# Controller.net
KiCad netlist of a schematic drawn in Altium Designer
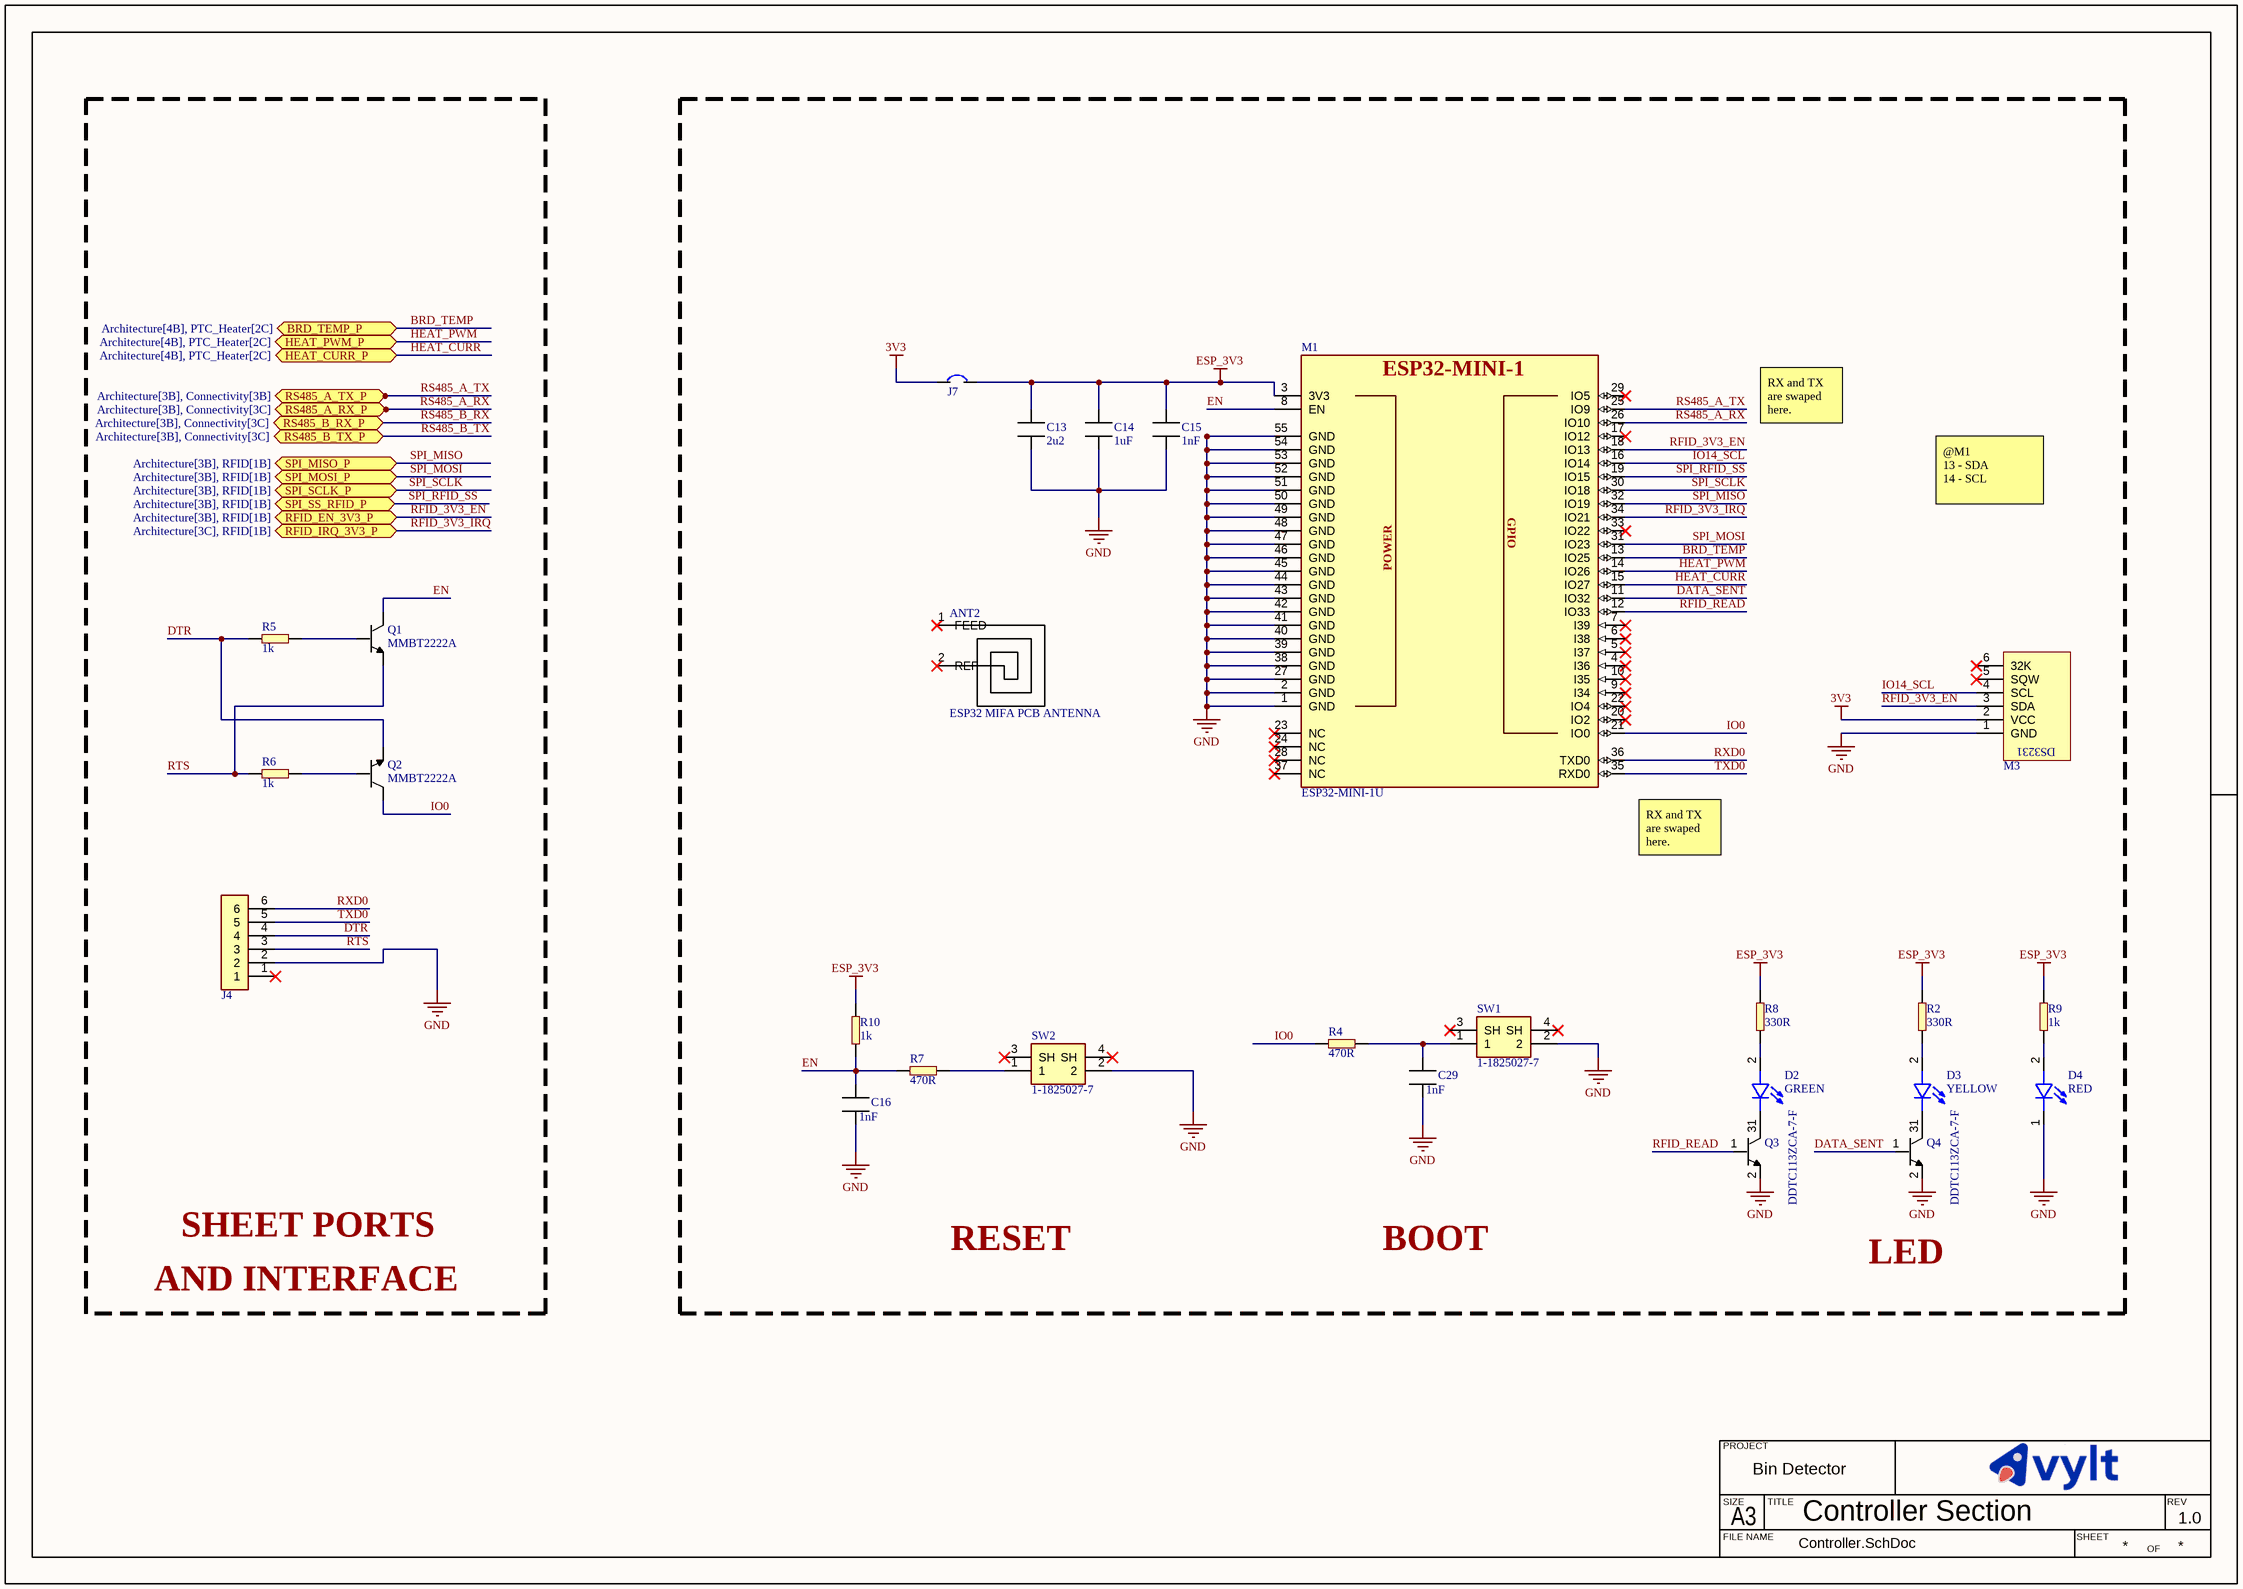
[diagram p0: Controller.SchDoc]

(export (version "E")
  (design (tool "Eeschema 10.0.6"))
  (components
    (comp (ref "ANT2")
      (value "ESP32 MIFA PCB ANTENNA")
      (footprint "ESP32 MIFA PCB ANTENNA")
      (libsource (lib "Antenna") (part "ESP32 MIFA PCB ANTENNA"))
    )
    (comp (ref "C13")
      (value "2u2")
      (footprint "CAPC1608X10N")
      (description "MLCC 0603")
      (fields (field (name "Comment") "ERP_102-1"))
      (libsource (lib "Capacitor") (part "MLCC_0603"))
    )
    (comp (ref "C14")
      (value "1uF")
      (footprint "CAPC1608X10N")
      (description "MLCC 0603")
      (fields (field (name "Comment") "ERP_102-1"))
      (libsource (lib "Capacitor") (part "MLCC_0603"))
    )
    (comp (ref "C15")
      (value "1nF")
      (footprint "CAPC1608X10N")
      (description "MLCC 0603")
      (fields (field (name "Comment") "ERP_102-1"))
      (libsource (lib "Capacitor") (part "MLCC_0603"))
    )
    (comp (ref "C16")
      (value "1nF")
      (footprint "CAPC1608X10N")
      (description "MLCC 0603")
      (fields (field (name "Comment") "ERP_102-1"))
      (libsource (lib "Capacitor") (part "MLCC_0603"))
    )
    (comp (ref "C29")
      (value "1nF")
      (footprint "CAPC1608X10N")
      (description "MLCC 0603")
      (fields (field (name "Comment") "ERP_102-1"))
      (libsource (lib "Capacitor") (part "MLCC_0603"))
    )
    (comp (ref "D2")
      (value "GREEN")
      (footprint "LED_2SMD")
      (description "LED GREEN CLEAR 1204 SMD R/A")
      (fields (field (name "Comment") "LED_2SMD"))
      (libsource (lib "LED") (part "LED_2SMD"))
    )
    (comp (ref "D3")
      (value "YELLOW")
      (footprint "LED_2SMD")
      (description "LED YELLOW CLEAR 1204 SMD R/A")
      (fields (field (name "Comment") "LED_2SMD"))
      (libsource (lib "LED") (part "LED_2SMD"))
    )
    (comp (ref "D4")
      (value "RED")
      (footprint "LED_2SMD")
      (description "LED RED CLEAR 1204 SMD R/A")
      (fields (field (name "Comment") "LED_2SMD"))
      (libsource (lib "LED") (part "LED_2SMD"))
    )
    (comp (ref "J4")
      (value "ERP_148-2")
      (footprint "6PX1R")
      (description "6PX1R")
      (libsource (lib "Male_Header_P2.54") (part "6PX1R"))
    )
    (comp (ref "J7")
      (value "Jumper_2P")
      (footprint "Jumper_2P")
      (description "Jumper 2 Pins")
      (libsource (lib "Jumper") (part "Jumper_2P"))
    )
    (comp (ref "M1")
      (value "ESP32-MINI-1U")
      (footprint "ESP32_MINI_1U")
      (description "ESP32_C3_MINI_1 Module")
      (fields (field (name "Comment") "ERP_140-3"))
      (libsource (lib "ESP") (part "ESP32_MINI_1"))
    )
    (comp (ref "M3")
      (value "DS3231_HW-084")
      (footprint "DS3231_HW-084")
      (description "DS3231 Time Module , HW-084")
      (libsource (lib "Time") (part "DS3231_HW-084"))
    )
    (comp (ref "Q1")
      (value "MMBT2222A")
      (footprint "MMBT2222")
      (fields (field (name "Comment") "ERP_105-1"))
      (libsource (lib "BJT") (part "MMBT2222"))
    )
    (comp (ref "Q2")
      (value "MMBT2222A")
      (footprint "MMBT2222")
      (fields (field (name "Comment") "ERP_105-1"))
      (libsource (lib "BJT") (part "MMBT2222"))
    )
    (comp (ref "Q3")
      (value "DDTC113ZCA-7-F")
      (footprint "DDTCXXXXCA")
      (description "TRANS PREBIAS NPN 50V SOT23-3")
      (fields (field (name "Comment") "ERP_105-1"))
      (libsource (lib "BJT") (part "DDTCXXXXCA"))
    )
    (comp (ref "Q4")
      (value "DDTC113ZCA-7-F")
      (footprint "DDTCXXXXCA")
      (description "TRANS PREBIAS NPN 50V SOT23-3")
      (fields (field (name "Comment") "ERP_105-1"))
      (libsource (lib "BJT") (part "DDTCXXXXCA"))
    )
    (comp (ref "R2")
      (value "330R")
      (footprint "RES_0603")
      (description "RES_0603")
      (fields (field (name "Comment") "ERP_101-1"))
      (libsource (lib "") (part "RES_0603_1"))
    )
    (comp (ref "R4")
      (value "470R")
      (footprint "RES_0603")
      (description "RES_0603")
      (fields (field (name "Comment") "ERP_101-1"))
      (libsource (lib "Resistor") (part "RES_0603"))
    )
    (comp (ref "R5")
      (value "1k")
      (footprint "RES_0603")
      (description "RES_0603")
      (fields (field (name "Comment") "ERP_101-1"))
      (libsource (lib "Resistor") (part "RES_0603"))
    )
    (comp (ref "R6")
      (value "1k")
      (footprint "RES_0603")
      (description "RES_0603")
      (fields (field (name "Comment") "ERP_101-1"))
      (libsource (lib "Resistor") (part "RES_0603"))
    )
    (comp (ref "R7")
      (value "470R")
      (footprint "RES_0603")
      (description "RES_0603")
      (fields (field (name "Comment") "ERP_101-1"))
      (libsource (lib "Resistor") (part "RES_0603"))
    )
    (comp (ref "R8")
      (value "330R")
      (footprint "RES_0603")
      (description "RES_0603")
      (fields (field (name "Comment") "ERP_101-1"))
      (libsource (lib "") (part "RES_0603_1"))
    )
    (comp (ref "R9")
      (value "1k")
      (footprint "RES_0603")
      (description "RES_0603")
      (fields (field (name "Comment") "ERP_101-1"))
      (libsource (lib "") (part "RES_0603_1"))
    )
    (comp (ref "R10")
      (value "1k")
      (footprint "RES_0603")
      (description "RES_0603")
      (fields (field (name "Comment") "ERP_101-1"))
      (libsource (lib "") (part "RES_0603_1"))
    )
    (comp (ref "SW1")
      (value "1-1825027-7")
      (footprint "FSM_6X6")
      (fields (field (name "Comment") "ERP_110-4"))
      (libsource (lib "Switch") (part "FSM_6X6"))
    )
    (comp (ref "SW2")
      (value "1-1825027-7")
      (footprint "FSM_6X6")
      (fields (field (name "Comment") "ERP_110-4"))
      (libsource (lib "Switch") (part "FSM_6X6"))
    )
  )
  (nets
    (net (code "2") (name "/BRD_TEMP") (class "Default")
      (node (ref "M1") (pin "13") (pinfunction "IO25_13") (pintype "bidirectional"))
    )
    (net (code "3") (name "/DATA_SENT") (class "Default")
      (node (ref "M1") (pin "11") (pinfunction "IO32_11") (pintype "bidirectional"))
      (node (ref "Q4") (pin "1") (pinfunction "1_1") (pintype "passive"))
    )
    (net (code "4") (name "/DTR") (class "Default")
      (node (ref "J4") (pin "4") (pinfunction "4_4") (pintype "passive"))
      (node (ref "Q2") (pin "2") (pinfunction "2_2") (pintype "passive"))
      (node (ref "R5") (pin "2") (pinfunction "2_2") (pintype "passive"))
    )
    (net (code "5") (name "/EN") (class "Default")
      (node (ref "C16") (pin "1") (pinfunction "1_1") (pintype "passive"))
      (node (ref "M1") (pin "8") (pinfunction "EN_8") (pintype "passive"))
      (node (ref "Q1") (pin "3") (pinfunction "3_3") (pintype "passive"))
      (node (ref "R10") (pin "1") (pinfunction "1_1") (pintype "passive"))
      (node (ref "R7") (pin "2") (pinfunction "2_2") (pintype "passive"))
    )
    (net (code "6") (name "/HEAT_CURR") (class "Default")
      (node (ref "M1") (pin "15") (pinfunction "IO27_15") (pintype "bidirectional"))
    )
    (net (code "7") (name "/HEAT_PWM") (class "Default")
      (node (ref "M1") (pin "14") (pinfunction "IO26_14") (pintype "bidirectional"))
    )
    (net (code "8") (name "/IO0") (class "Default")
      (node (ref "M1") (pin "21") (pinfunction "IO0_21") (pintype "bidirectional"))
      (node (ref "Q2") (pin "3") (pinfunction "3_3") (pintype "passive"))
      (node (ref "R4") (pin "2") (pinfunction "2_2") (pintype "passive"))
    )
    (net (code "9") (name "/IO14_SCL") (class "Default")
      (node (ref "M1") (pin "16") (pinfunction "IO14_16") (pintype "bidirectional"))
      (node (ref "M3") (pin "4") (pinfunction "SCL_4") (pintype "passive"))
    )
    (net (code "10") (name "/RFID_3V3_EN") (class "Default")
      (node (ref "M1") (pin "18") (pinfunction "IO13_18") (pintype "bidirectional"))
      (node (ref "M3") (pin "3") (pinfunction "SDA_3") (pintype "passive"))
    )
    (net (code "11") (name "/RFID_3V3_IRQ") (class "Default")
      (node (ref "M1") (pin "34") (pinfunction "IO21_34") (pintype "bidirectional"))
    )
    (net (code "12") (name "/RFID_READ") (class "Default")
      (node (ref "M1") (pin "12") (pinfunction "IO33_12") (pintype "bidirectional"))
      (node (ref "Q3") (pin "1") (pinfunction "1_1") (pintype "passive"))
    )
    (net (code "13") (name "/RS485_A_RX") (class "Default")
      (node (ref "M1") (pin "26") (pinfunction "IO10_26") (pintype "bidirectional"))
    )
    (net (code "14") (name "/RS485_A_TX") (class "Default")
      (node (ref "M1") (pin "25") (pinfunction "IO9_25") (pintype "bidirectional"))
    )
    (net (code "17") (name "/RTS") (class "Default")
      (node (ref "J4") (pin "3") (pinfunction "3_3") (pintype "passive"))
      (node (ref "Q1") (pin "2") (pinfunction "2_2") (pintype "passive"))
      (node (ref "R6") (pin "2") (pinfunction "2_2") (pintype "passive"))
    )
    (net (code "18") (name "/RXD0") (class "Default")
      (node (ref "J4") (pin "6") (pinfunction "6_6") (pintype "passive"))
      (node (ref "M1") (pin "36") (pinfunction "TXD0_36") (pintype "bidirectional"))
    )
    (net (code "19") (name "/SPI_MISO") (class "Default")
      (node (ref "M1") (pin "32") (pinfunction "IO19_32") (pintype "bidirectional"))
    )
    (net (code "20") (name "/SPI_MOSI") (class "Default")
      (node (ref "M1") (pin "31") (pinfunction "IO23_31") (pintype "bidirectional"))
    )
    (net (code "21") (name "/SPI_RFID_SS") (class "Default")
      (node (ref "M1") (pin "19") (pinfunction "IO15_19") (pintype "bidirectional"))
    )
    (net (code "22") (name "/SPI_SCLK") (class "Default")
      (node (ref "M1") (pin "30") (pinfunction "IO18_30") (pintype "bidirectional"))
    )
    (net (code "23") (name "/TXD0") (class "Default")
      (node (ref "J4") (pin "5") (pinfunction "5_5") (pintype "passive"))
      (node (ref "M1") (pin "35") (pinfunction "RXD0_35") (pintype "bidirectional"))
    )
    (net (code "24") (name "3V3") (class "Default")
      (node (ref "J7") (pin "1") (pintype "passive"))
      (node (ref "M3") (pin "2") (pinfunction "VCC_2") (pintype "passive"))
    )
    (net (code "25") (name "ESP_3V3") (class "Default")
      (node (ref "C13") (pin "2") (pinfunction "2_2") (pintype "passive"))
      (node (ref "C14") (pin "2") (pinfunction "2_2") (pintype "passive"))
      (node (ref "C15") (pin "2") (pinfunction "2_2") (pintype "passive"))
      (node (ref "J7") (pin "2") (pintype "passive"))
      (node (ref "M1") (pin "3") (pinfunction "3V3_3") (pintype "power_in"))
      (node (ref "R10") (pin "2") (pinfunction "2_2") (pintype "passive"))
      (node (ref "R2") (pin "2") (pinfunction "2_2") (pintype "passive"))
      (node (ref "R8") (pin "2") (pinfunction "2_2") (pintype "passive"))
      (node (ref "R9") (pin "2") (pinfunction "2_2") (pintype "passive"))
    )
    (net (code "26") (name "GND") (class "Default")
      (node (ref "C13") (pin "1") (pinfunction "1_1") (pintype "passive"))
      (node (ref "C14") (pin "1") (pinfunction "1_1") (pintype "passive"))
      (node (ref "C15") (pin "1") (pinfunction "1_1") (pintype "passive"))
      (node (ref "C16") (pin "2") (pinfunction "2_2") (pintype "passive"))
      (node (ref "C29") (pin "2") (pinfunction "2_2") (pintype "passive"))
      (node (ref "D4") (pin "1") (pinfunction "1_1") (pintype "passive"))
      (node (ref "J4") (pin "2") (pinfunction "2_2") (pintype "passive"))
      (node (ref "M1") (pin "1") (pinfunction "GND_1") (pintype "passive"))
      (node (ref "M1") (pin "2") (pinfunction "GND_2") (pintype "passive"))
      (node (ref "M1") (pin "27") (pinfunction "GND_27") (pintype "passive"))
      (node (ref "M1") (pin "38") (pinfunction "GND_38") (pintype "passive"))
      (node (ref "M1") (pin "39") (pinfunction "GND_39") (pintype "passive"))
      (node (ref "M1") (pin "40") (pinfunction "GND_40") (pintype "passive"))
      (node (ref "M1") (pin "41") (pinfunction "GND_41") (pintype "passive"))
      (node (ref "M1") (pin "42") (pinfunction "GND_42") (pintype "passive"))
      (node (ref "M1") (pin "43") (pinfunction "GND_43") (pintype "passive"))
      (node (ref "M1") (pin "44") (pinfunction "GND_44") (pintype "passive"))
      (node (ref "M1") (pin "45") (pinfunction "GND_45") (pintype "passive"))
      (node (ref "M1") (pin "46") (pinfunction "GND_46") (pintype "passive"))
      (node (ref "M1") (pin "47") (pinfunction "GND_47") (pintype "passive"))
      (node (ref "M1") (pin "48") (pinfunction "GND_48") (pintype "passive"))
      (node (ref "M1") (pin "49") (pinfunction "GND_49") (pintype "passive"))
      (node (ref "M1") (pin "50") (pinfunction "GND_50") (pintype "passive"))
      (node (ref "M1") (pin "51") (pinfunction "GND_51") (pintype "passive"))
      (node (ref "M1") (pin "52") (pinfunction "GND_52") (pintype "passive"))
      (node (ref "M1") (pin "53") (pinfunction "GND_53") (pintype "passive"))
      (node (ref "M1") (pin "54") (pinfunction "GND_54") (pintype "passive"))
      (node (ref "M1") (pin "55") (pinfunction "GND_55") (pintype "passive"))
      (node (ref "M3") (pin "1") (pinfunction "GND_1") (pintype "passive"))
      (node (ref "Q3") (pin "2") (pinfunction "2_2") (pintype "passive"))
      (node (ref "Q4") (pin "2") (pinfunction "2_2") (pintype "passive"))
      (node (ref "SW1") (pin "2") (pinfunction "2_2") (pintype "passive"))
      (node (ref "SW2") (pin "2") (pinfunction "2_2") (pintype "passive"))
    )
    (net (code "27") (name "Net-(C29-Pad1)") (class "Default")
      (node (ref "C29") (pin "1") (pinfunction "1_1") (pintype "passive"))
      (node (ref "R4") (pin "1") (pinfunction "1_1") (pintype "passive"))
      (node (ref "SW1") (pin "1") (pinfunction "1_1") (pintype "passive"))
    )
    (net (code "28") (name "Net-(D2-Pad1)") (class "Default")
      (node (ref "D2") (pin "1") (pinfunction "1_1") (pintype "passive"))
      (node (ref "Q3") (pin "3") (pinfunction "3_3") (pintype "passive"))
    )
    (net (code "29") (name "Net-(D2-Pad2)") (class "Default")
      (node (ref "D2") (pin "2") (pinfunction "2_2") (pintype "passive"))
      (node (ref "R8") (pin "1") (pinfunction "1_1") (pintype "passive"))
    )
    (net (code "30") (name "Net-(D3-Pad1)") (class "Default")
      (node (ref "D3") (pin "1") (pinfunction "1_1") (pintype "passive"))
      (node (ref "Q4") (pin "3") (pinfunction "3_3") (pintype "passive"))
    )
    (net (code "31") (name "Net-(D3-Pad2)") (class "Default")
      (node (ref "D3") (pin "2") (pinfunction "2_2") (pintype "passive"))
      (node (ref "R2") (pin "1") (pinfunction "1_1") (pintype "passive"))
    )
    (net (code "32") (name "Net-(D4-Pad2)") (class "Default")
      (node (ref "D4") (pin "2") (pinfunction "2_2") (pintype "passive"))
      (node (ref "R9") (pin "1") (pinfunction "1_1") (pintype "passive"))
    )
    (net (code "33") (name "Net-(Q1-Pad1)") (class "Default")
      (node (ref "Q1") (pin "1") (pinfunction "1_1") (pintype "passive"))
      (node (ref "R5") (pin "1") (pinfunction "1_1") (pintype "passive"))
    )
    (net (code "34") (name "Net-(Q2-Pad1)") (class "Default")
      (node (ref "Q2") (pin "1") (pinfunction "1_1") (pintype "passive"))
      (node (ref "R6") (pin "1") (pinfunction "1_1") (pintype "passive"))
    )
    (net (code "35") (name "Net-(R7-Pad1)") (class "Default")
      (node (ref "R7") (pin "1") (pinfunction "1_1") (pintype "passive"))
      (node (ref "SW2") (pin "1") (pinfunction "1_1") (pintype "passive"))
    )
    (net (code "36") (name "unconnected-(ANT2-FEED-Pad1)") (class "Default")
      (node (ref "ANT2") (pin "1") (pinfunction "FEED_1") (pintype "passive+no_connect"))
    )
    (net (code "37") (name "unconnected-(ANT2-REF-Pad2)") (class "Default")
      (node (ref "ANT2") (pin "2") (pinfunction "REF_2") (pintype "passive+no_connect"))
    )
    (net (code "38") (name "unconnected-(J4-Pad1)") (class "Default")
      (node (ref "J4") (pin "1") (pinfunction "1_1") (pintype "passive+no_connect"))
    )
    (net (code "39") (name "unconnected-(M1-I34-Pad9)") (class "Default")
      (node (ref "M1") (pin "9") (pinfunction "I34_9") (pintype "input+no_connect"))
    )
    (net (code "40") (name "unconnected-(M1-I35-Pad10)") (class "Default")
      (node (ref "M1") (pin "10") (pinfunction "I35_10") (pintype "input+no_connect"))
    )
    (net (code "41") (name "unconnected-(M1-I36-Pad4)") (class "Default")
      (node (ref "M1") (pin "4") (pinfunction "I36_4") (pintype "input+no_connect"))
    )
    (net (code "42") (name "unconnected-(M1-I37-Pad5)") (class "Default")
      (node (ref "M1") (pin "5") (pinfunction "I37_5") (pintype "input+no_connect"))
    )
    (net (code "43") (name "unconnected-(M1-I38-Pad6)") (class "Default")
      (node (ref "M1") (pin "6") (pinfunction "I38_6") (pintype "input+no_connect"))
    )
    (net (code "44") (name "unconnected-(M1-I39-Pad7)") (class "Default")
      (node (ref "M1") (pin "7") (pinfunction "I39_7") (pintype "input+no_connect"))
    )
    (net (code "45") (name "unconnected-(M1-IO2-Pad20)") (class "Default")
      (node (ref "M1") (pin "20") (pinfunction "IO2_20") (pintype "bidirectional+no_connect"))
    )
    (net (code "46") (name "unconnected-(M1-IO4-Pad22)") (class "Default")
      (node (ref "M1") (pin "22") (pinfunction "IO4_22") (pintype "bidirectional+no_connect"))
    )
    (net (code "47") (name "unconnected-(M1-IO5-Pad29)") (class "Default")
      (node (ref "M1") (pin "29") (pinfunction "IO5_29") (pintype "bidirectional+no_connect"))
    )
    (net (code "48") (name "unconnected-(M1-IO12-Pad17)") (class "Default")
      (node (ref "M1") (pin "17") (pinfunction "IO12_17") (pintype "bidirectional+no_connect"))
    )
    (net (code "49") (name "unconnected-(M1-IO22-Pad33)") (class "Default")
      (node (ref "M1") (pin "33") (pinfunction "IO22_33") (pintype "bidirectional+no_connect"))
    )
    (net (code "50") (name "unconnected-(M1-NC-Pad23)") (class "Default")
      (node (ref "M1") (pin "23") (pinfunction "NC_23") (pintype "passive+no_connect"))
    )
    (net (code "51") (name "unconnected-(M1-NC-Pad24)") (class "Default")
      (node (ref "M1") (pin "24") (pinfunction "NC_24") (pintype "passive+no_connect"))
    )
    (net (code "52") (name "unconnected-(M1-NC-Pad28)") (class "Default")
      (node (ref "M1") (pin "28") (pinfunction "NC_28") (pintype "passive+no_connect"))
    )
    (net (code "53") (name "unconnected-(M1-NC-Pad37)") (class "Default")
      (node (ref "M1") (pin "37") (pinfunction "NC_37") (pintype "passive+no_connect"))
    )
    (net (code "54") (name "unconnected-(M3-32K-Pad6)") (class "Default")
      (node (ref "M3") (pin "6") (pinfunction "32K_6") (pintype "passive+no_connect"))
    )
    (net (code "55") (name "unconnected-(M3-SQW-Pad5)") (class "Default")
      (node (ref "M3") (pin "5") (pinfunction "SQW_5") (pintype "passive+no_connect"))
    )
    (net (code "56") (name "unconnected-(SW1-SH-Pad3)") (class "Default")
      (node (ref "SW1") (pin "3") (pinfunction "SH_3") (pintype "passive+no_connect"))
    )
    (net (code "57") (name "unconnected-(SW1-SH-Pad4)") (class "Default")
      (node (ref "SW1") (pin "4") (pinfunction "SH_4") (pintype "passive+no_connect"))
    )
    (net (code "58") (name "unconnected-(SW2-SH-Pad3)") (class "Default")
      (node (ref "SW2") (pin "3") (pinfunction "SH_3") (pintype "passive+no_connect"))
    )
    (net (code "59") (name "unconnected-(SW2-SH-Pad4)") (class "Default")
      (node (ref "SW2") (pin "4") (pinfunction "SH_4") (pintype "passive+no_connect"))
    )
  )
)
